# WaterDetector.net
KiCad netlist of a schematic drawn in EAGLE
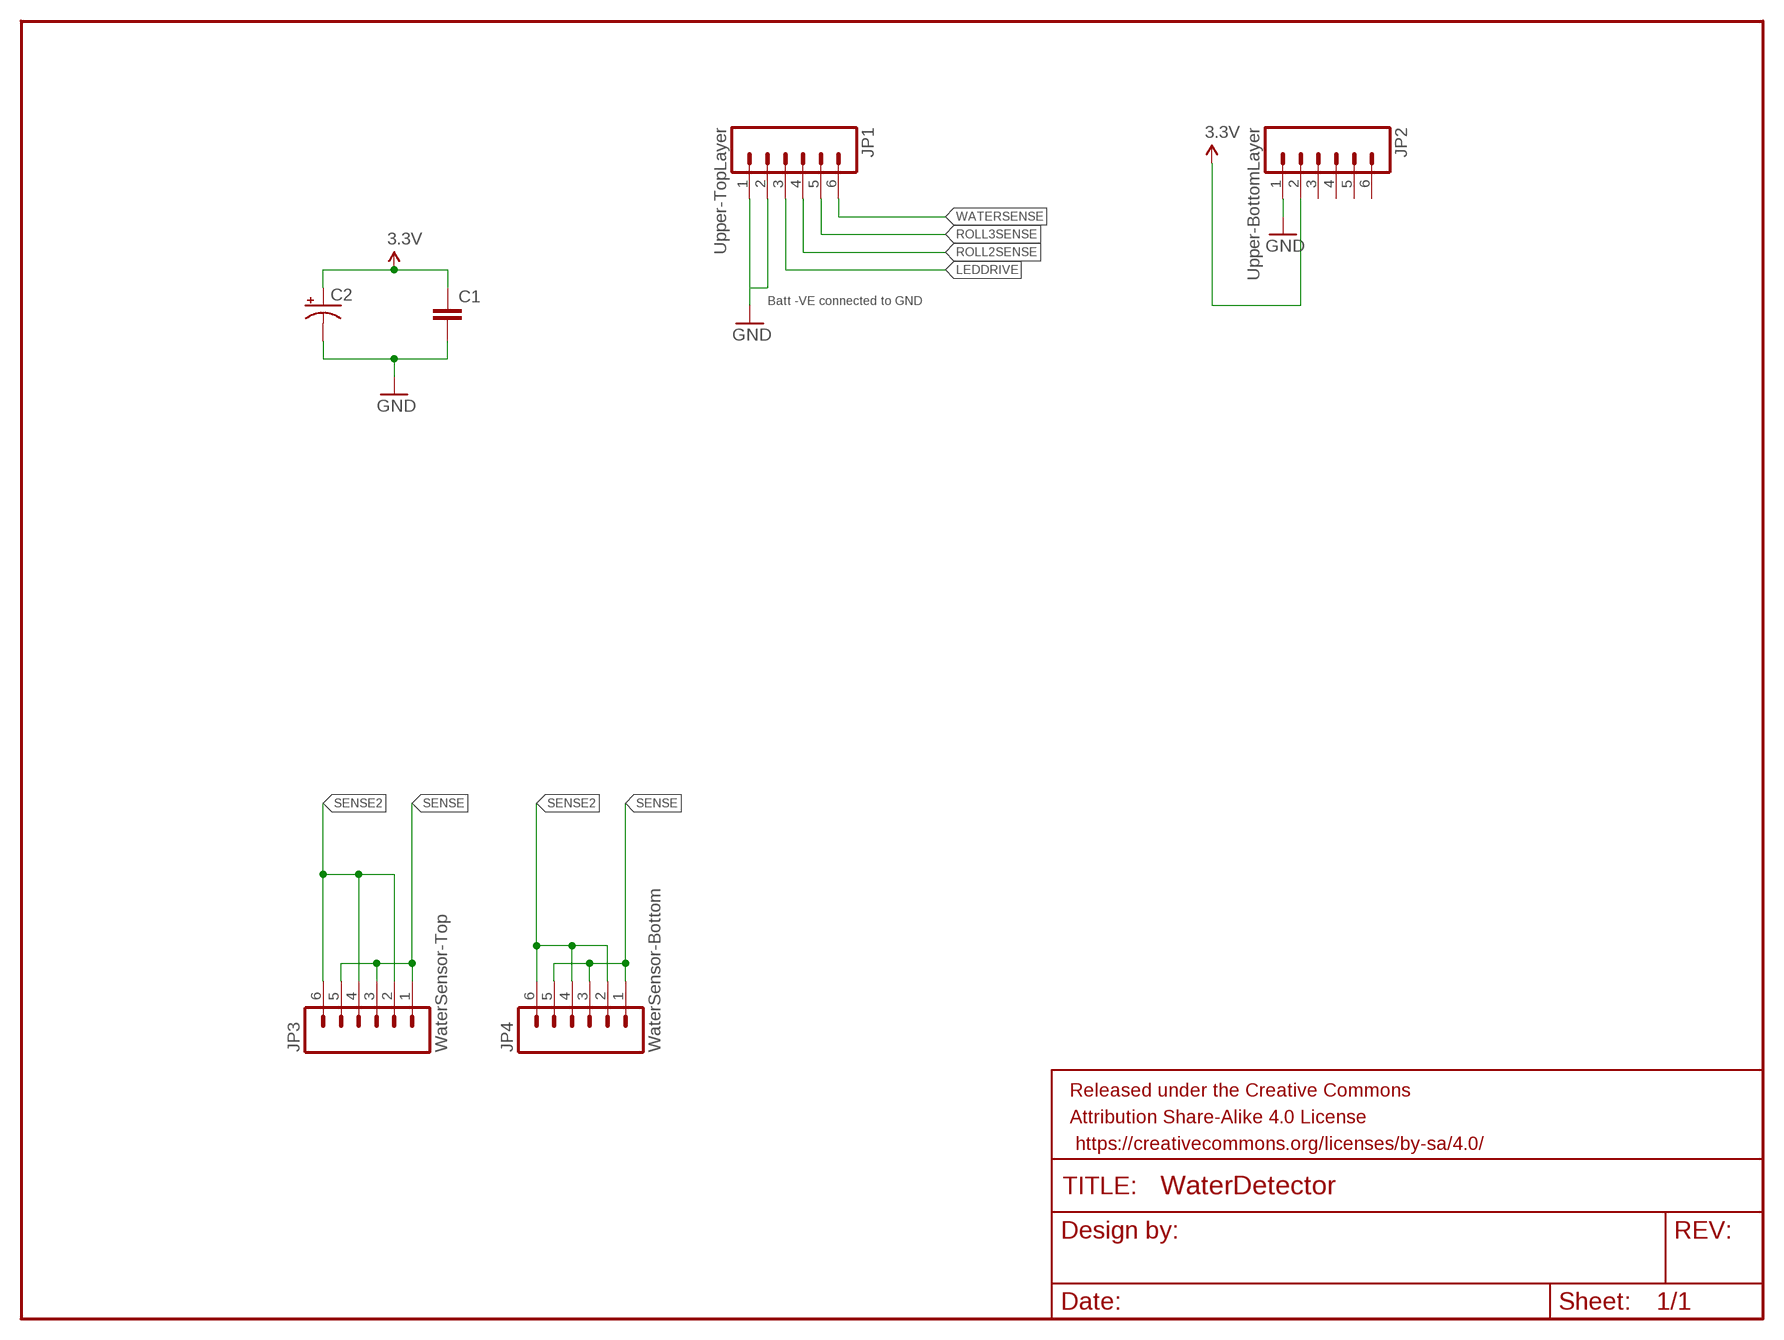
[diagram p0: schematic, sheet 1]

(export (version "E")
  (design (tool "Eeschema 10.0.6"))
  (components
    (comp (ref "C1")
      (value "CAP0805")
      (footprint "eagle-import:0805")
      (libsource (lib "eagle-import") (part "CAP0805"))
    )
    (comp (ref "C2")
      (value "CAP_POLC")
      (footprint "eagle-import:PANASONIC_C")
      (libsource (lib "eagle-import") (part "CAP_POLC"))
    )
    (comp (ref "FRAME1")
      (value "FRAME-LETTER")
      (footprint "eagle-import:CREATIVE_COMMONS")
      (libsource (lib "eagle-import") (part "FRAME-LETTER"))
    )
    (comp (ref "JP1")
      (value "Upper-TopLayer")
      (footprint "eagle-import:1X06-SMD_EDGE")
      (libsource (lib "eagle-import") (part "M061X06-SMD-EDGE-SOLDERLINK1X06-SMD-EDGE-SOLDERLINK"))
    )
    (comp (ref "JP2")
      (value "Upper-BottomLayer")
      (footprint "eagle-import:1X06-SMD_EDGE")
      (libsource (lib "eagle-import") (part "M061X06-SMD-EDGE-SOLDERLINK1X06-SMD-EDGE-SOLDERLINK"))
    )
    (comp (ref "JP3")
      (value "WaterSensor-Top")
      (footprint "eagle-import:1X06-SMD_EDGE")
      (libsource (lib "eagle-import") (part "M061X06-SMD-EDGE-SOLDERLINK1X06-SMD-EDGE-SOLDERLINK"))
    )
    (comp (ref "JP4")
      (value "WaterSensor-Bottom")
      (footprint "eagle-import:1X06-SMD_EDGE")
      (libsource (lib "eagle-import") (part "M061X06-SMD-EDGE-SOLDERLINK1X06-SMD-EDGE-SOLDERLINK"))
    )
  )
  (nets
    (net (code "1") (name "3.3V") (class "Default")
      (node (ref "C1") (pin "1") (pinfunction "1_1") (pintype "passive"))
      (node (ref "C2") (pin "+") (pinfunction "+_+") (pintype "passive"))
      (node (ref "JP2") (pin "2") (pinfunction "2_2") (pintype "passive"))
    )
    (net (code "2") (name "GND") (class "Default")
      (node (ref "C1") (pin "2") (pinfunction "2_2") (pintype "passive"))
      (node (ref "C2") (pin "-") (pinfunction "-_-") (pintype "passive"))
      (node (ref "JP1") (pin "1") (pinfunction "1_1") (pintype "passive"))
      (node (ref "JP1") (pin "2") (pinfunction "2_2") (pintype "passive"))
      (node (ref "JP2") (pin "1") (pinfunction "1_1") (pintype "passive"))
    )
    (net (code "3") (name "LEDDRIVE") (class "Default")
      (node (ref "JP1") (pin "3") (pinfunction "3_3") (pintype "passive"))
    )
    (net (code "4") (name "ROLL2SENSE") (class "Default")
      (node (ref "JP1") (pin "4") (pinfunction "4_4") (pintype "passive"))
    )
    (net (code "5") (name "ROLL3SENSE") (class "Default")
      (node (ref "JP1") (pin "5") (pinfunction "5_5") (pintype "passive"))
    )
    (net (code "6") (name "SENSE") (class "Default")
      (node (ref "JP3") (pin "1") (pinfunction "1_1") (pintype "passive"))
      (node (ref "JP3") (pin "3") (pinfunction "3_3") (pintype "passive"))
      (node (ref "JP3") (pin "5") (pinfunction "5_5") (pintype "passive"))
      (node (ref "JP4") (pin "1") (pinfunction "1_1") (pintype "passive"))
      (node (ref "JP4") (pin "3") (pinfunction "3_3") (pintype "passive"))
      (node (ref "JP4") (pin "5") (pinfunction "5_5") (pintype "passive"))
    )
    (net (code "7") (name "SENSE2") (class "Default")
      (node (ref "JP3") (pin "2") (pinfunction "2_2") (pintype "passive"))
      (node (ref "JP3") (pin "4") (pinfunction "4_4") (pintype "passive"))
      (node (ref "JP3") (pin "6") (pinfunction "6_6") (pintype "passive"))
      (node (ref "JP4") (pin "2") (pinfunction "2_2") (pintype "passive"))
      (node (ref "JP4") (pin "4") (pinfunction "4_4") (pintype "passive"))
      (node (ref "JP4") (pin "6") (pinfunction "6_6") (pintype "passive"))
    )
    (net (code "8") (name "WATERSENSE") (class "Default")
      (node (ref "JP1") (pin "6") (pinfunction "6_6") (pintype "passive"))
    )
    (net (code "9") (name "unconnected-(JP2-Pad3)") (class "Default")
      (node (ref "JP2") (pin "3") (pinfunction "3_3") (pintype "passive"))
    )
    (net (code "10") (name "unconnected-(JP2-Pad4)") (class "Default")
      (node (ref "JP2") (pin "4") (pinfunction "4_4") (pintype "passive"))
    )
    (net (code "11") (name "unconnected-(JP2-Pad5)") (class "Default")
      (node (ref "JP2") (pin "5") (pinfunction "5_5") (pintype "passive"))
    )
    (net (code "12") (name "unconnected-(JP2-Pad6)") (class "Default")
      (node (ref "JP2") (pin "6") (pinfunction "6_6") (pintype "passive"))
    )
  )
)
